# Schematic.net
KiCad netlist of a schematic drawn in EasyEDA
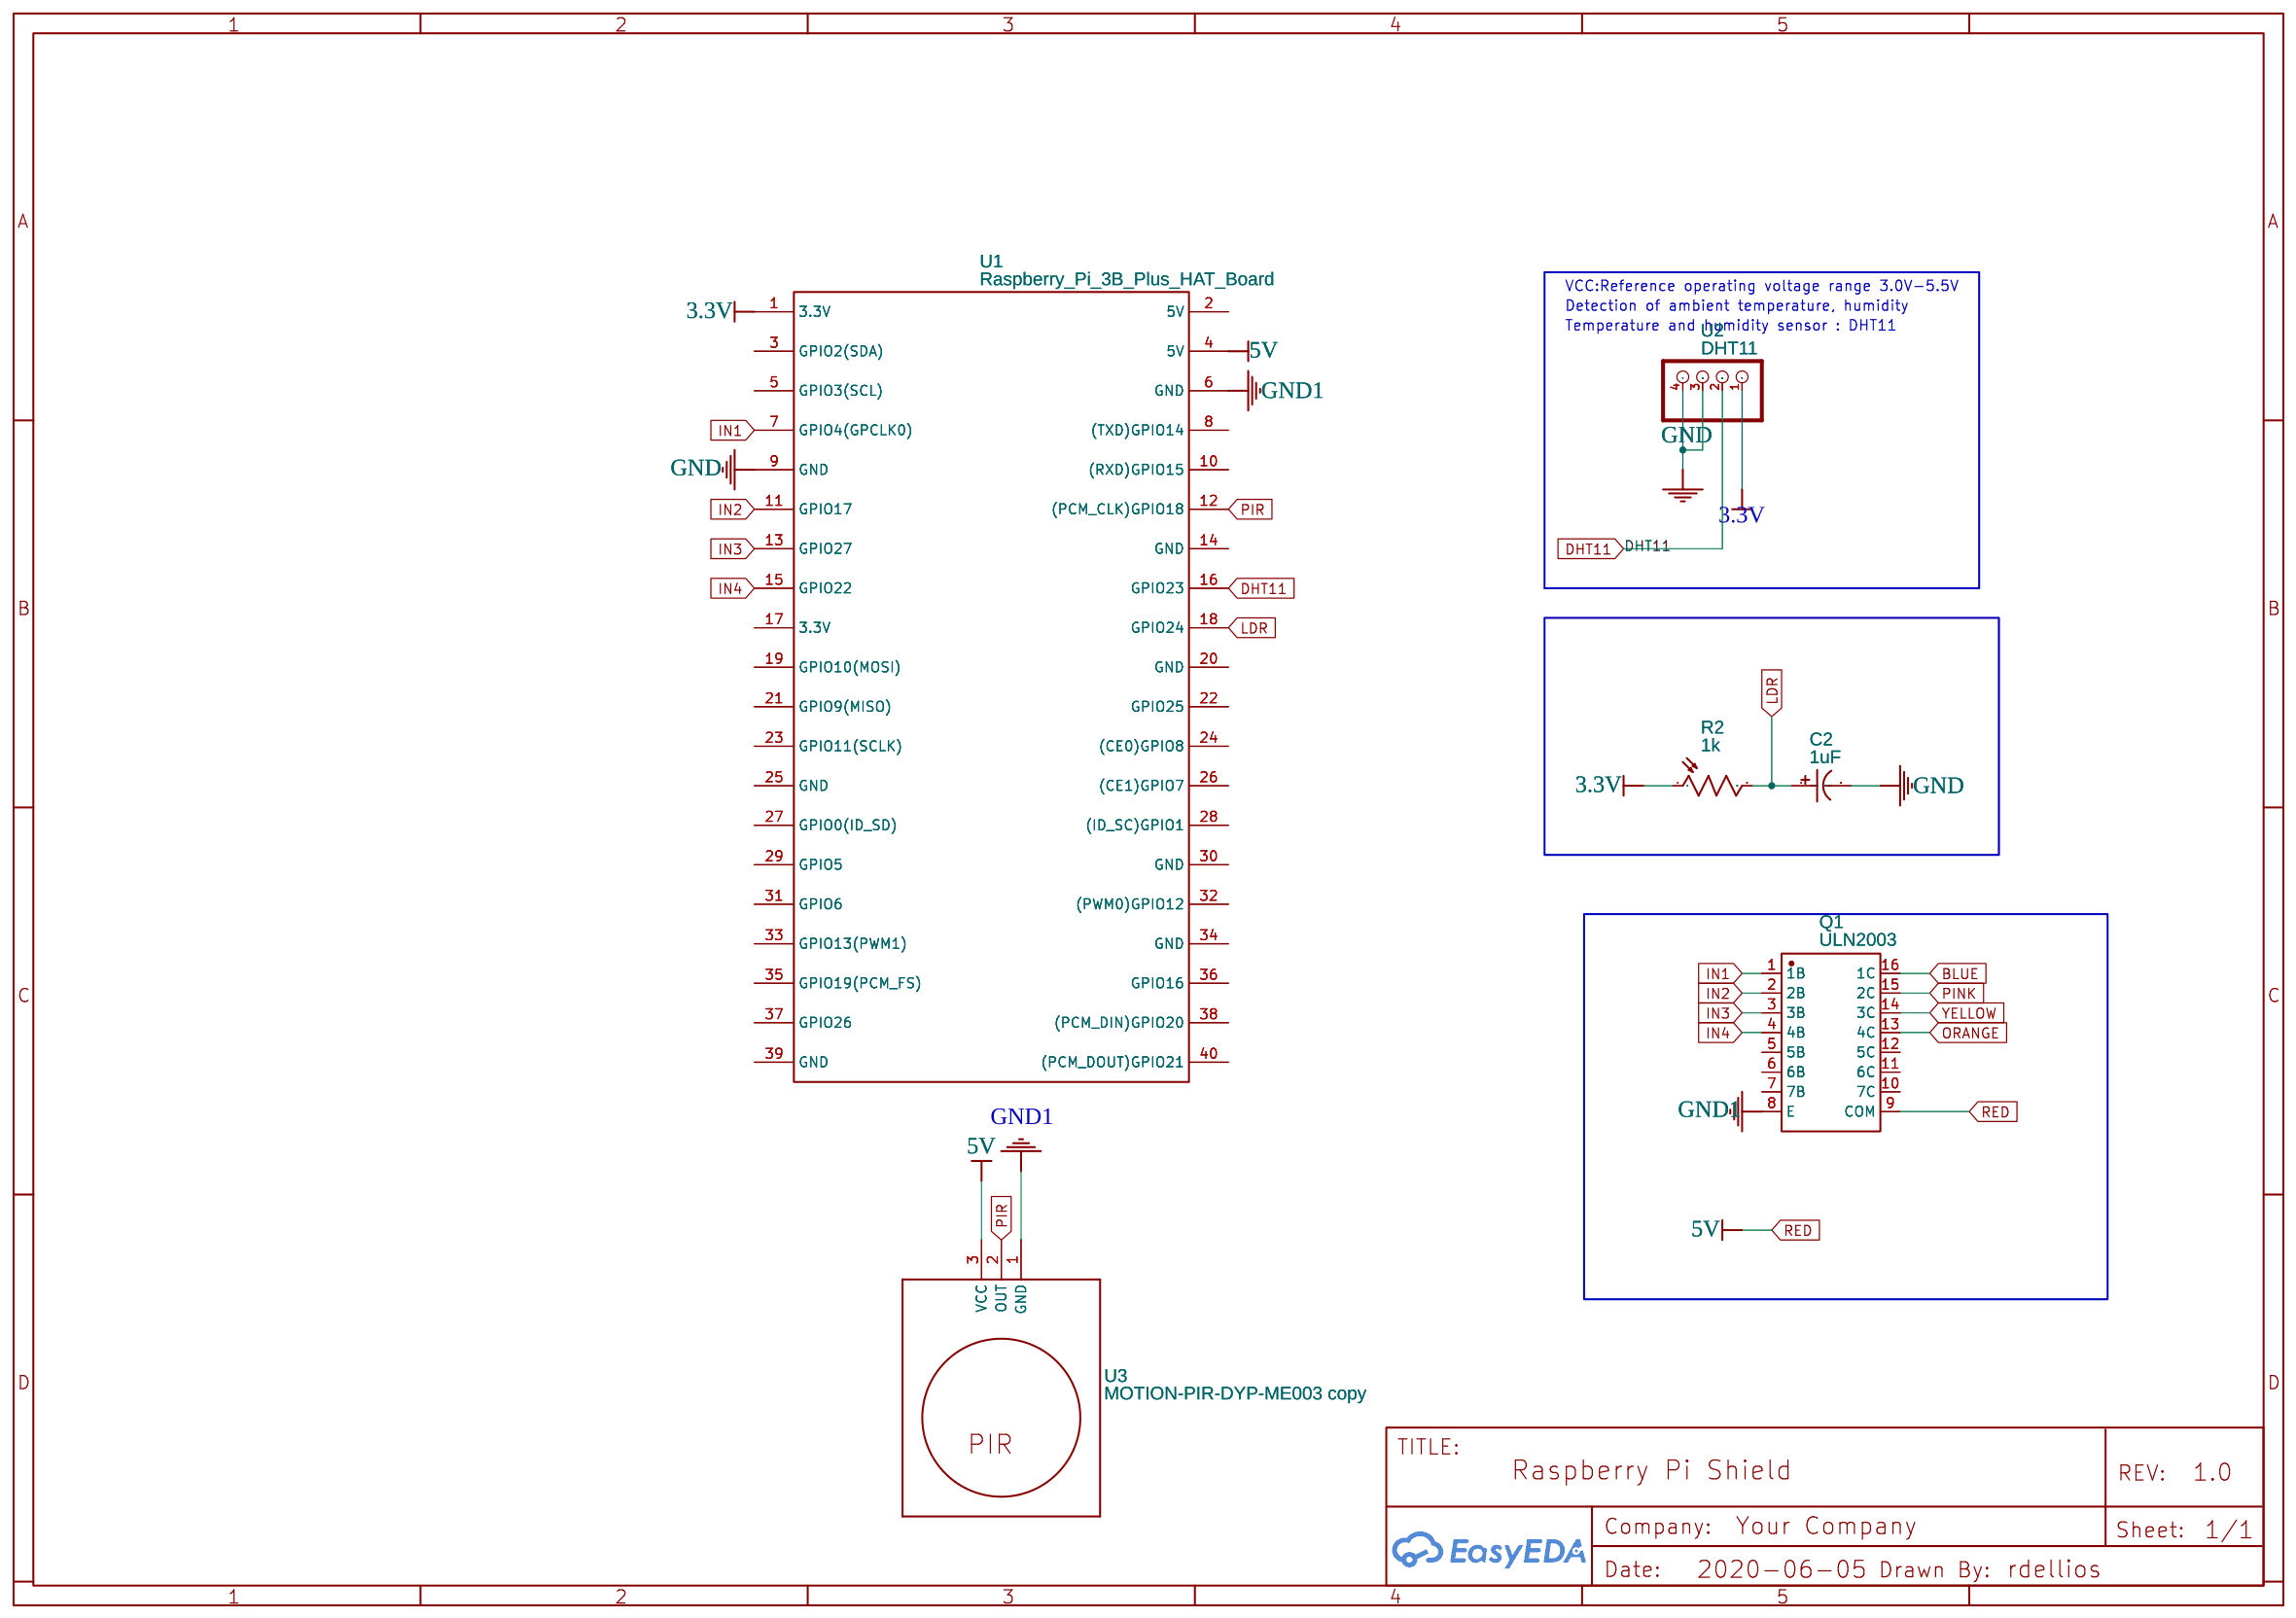
[diagram p0: schematic sheet]

(export (version "E")
  (design (tool "Eeschema 10.0.6"))
  (components
    (comp (ref "C2")
      (value "1uF")
      (fields
        (field (name "BOM_Manufacturer Part") "1uF 50V 4*5")
        (field (name "BOM_Supplier Part") "C47848")
      )
      (libsource (lib "") (part "1uF 50V 4*5"))
    )
    (comp (ref "Q1")
      (value "ULN2003")
      (fields (field (name "BOM_Supplier Part") "C411052"))
      (libsource (lib "") (part "ULN2003"))
    )
    (comp (ref "R2") (value "1k") (libsource (lib "") (part "PhotoResistor")))
    (comp (ref "U1")
      (value "Raspberry_Pi_3B_Plus_HAT_Board")
      (fields (field (name "BOM_Manufacturer Part") "Raspberry-Pi-3B-Plus-HAT-Board"))
      (libsource (lib "") (part "Raspberry_Pi_3B_Plus_HAT_Board"))
    )
    (comp (ref "U2")
      (value "DHT11")
      (fields (field (name "BOM_Manufacturer Part") "?"))
      (libsource (lib "") (part "Unknown_825_-595"))
    )
    (comp (ref "U3")
      (value "MOTION-PIR-DYP-ME003 copy")
      (libsource (lib "") (part "MOTION-PIR-DYP-ME003 copy"))
    )
  )
  (nets
    (net (code "1") (name "3.3V") (class "Default")
      (node (ref "R2") (pin "1") (pinfunction "1_1") (pintype "unspecified"))
      (node (ref "U1") (pin "1") (pinfunction "3.3V_1") (pintype "unspecified"))
      (node (ref "U2") (pin "1") (pinfunction "1_1") (pintype "unspecified"))
    )
    (net (code "2") (name "BLUE") (class "Default")
      (node (ref "Q1") (pin "16") (pinfunction "1C_16") (pintype "unspecified"))
    )
    (net (code "3") (name "DHT11") (class "Default")
      (node (ref "U1") (pin "16") (pinfunction "GPIO23_16") (pintype "unspecified"))
      (node (ref "U2") (pin "2") (pinfunction "2_2") (pintype "unspecified"))
    )
    (net (code "4") (name "GND") (class "Default")
      (node (ref "C2") (pin "2") (pinfunction "2_2") (pintype "input"))
      (node (ref "U1") (pin "9") (pinfunction "GND_9") (pintype "unspecified"))
      (node (ref "U2") (pin "3") (pinfunction "3_3") (pintype "unspecified"))
      (node (ref "U2") (pin "4") (pinfunction "4_4") (pintype "unspecified"))
    )
    (net (code "5") (name "GND1") (class "Default")
      (node (ref "Q1") (pin "8") (pinfunction "E_8") (pintype "unspecified"))
      (node (ref "U1") (pin "6") (pinfunction "GND_6") (pintype "unspecified"))
      (node (ref "U3") (pin "1") (pinfunction "GND_1") (pintype "passive"))
    )
    (net (code "6") (name "IN1") (class "Default")
      (node (ref "Q1") (pin "1") (pinfunction "1B_1") (pintype "unspecified"))
      (node (ref "U1") (pin "7") (pinfunction "GPIO4(GPCLK0)_7") (pintype "unspecified"))
    )
    (net (code "7") (name "IN2") (class "Default")
      (node (ref "Q1") (pin "2") (pinfunction "2B_2") (pintype "unspecified"))
      (node (ref "U1") (pin "11") (pinfunction "GPIO17_11") (pintype "unspecified"))
    )
    (net (code "8") (name "IN3") (class "Default")
      (node (ref "Q1") (pin "3") (pinfunction "3B_3") (pintype "unspecified"))
      (node (ref "U1") (pin "13") (pinfunction "GPIO27_13") (pintype "unspecified"))
    )
    (net (code "9") (name "IN4") (class "Default")
      (node (ref "Q1") (pin "4") (pinfunction "4B_4") (pintype "unspecified"))
      (node (ref "U1") (pin "15") (pinfunction "GPIO22_15") (pintype "unspecified"))
    )
    (net (code "10") (name "LDR") (class "Default")
      (node (ref "C2") (pin "1") (pinfunction "1_1") (pintype "input"))
      (node (ref "R2") (pin "2") (pinfunction "2_2") (pintype "unspecified"))
      (node (ref "U1") (pin "18") (pinfunction "GPIO24_18") (pintype "unspecified"))
    )
    (net (code "11") (name "ORANGE") (class "Default")
      (node (ref "Q1") (pin "13") (pinfunction "4C_13") (pintype "unspecified"))
    )
    (net (code "12") (name "PINK") (class "Default")
      (node (ref "Q1") (pin "15") (pinfunction "2C_15") (pintype "unspecified"))
    )
    (net (code "13") (name "PIR") (class "Default")
      (node (ref "U1") (pin "12") (pinfunction "(PCM_CLK)GPIO18_12") (pintype "unspecified"))
      (node (ref "U3") (pin "2") (pinfunction "OUT_2") (pintype "output"))
    )
    (net (code "14") (name "RED") (class "Default")
      (node (ref "Q1") (pin "9") (pinfunction "COM_9") (pintype "unspecified"))
      (node (ref "U1") (pin "4") (pinfunction "5V_4") (pintype "unspecified"))
      (node (ref "U3") (pin "3") (pinfunction "VCC_3") (pintype "passive"))
    )
    (net (code "15") (name "YELLOW") (class "Default")
      (node (ref "Q1") (pin "14") (pinfunction "3C_14") (pintype "unspecified"))
    )
    (net (code "16") (name "unconnected-(Q1-5B-Pad5)") (class "Default")
      (node (ref "Q1") (pin "5") (pinfunction "5B_5") (pintype "unspecified"))
    )
    (net (code "17") (name "unconnected-(Q1-5C-Pad12)") (class "Default")
      (node (ref "Q1") (pin "12") (pinfunction "5C_12") (pintype "unspecified"))
    )
    (net (code "18") (name "unconnected-(Q1-6B-Pad6)") (class "Default")
      (node (ref "Q1") (pin "6") (pinfunction "6B_6") (pintype "unspecified"))
    )
    (net (code "19") (name "unconnected-(Q1-6C-Pad11)") (class "Default")
      (node (ref "Q1") (pin "11") (pinfunction "6C_11") (pintype "unspecified"))
    )
    (net (code "20") (name "unconnected-(Q1-7B-Pad7)") (class "Default")
      (node (ref "Q1") (pin "7") (pinfunction "7B_7") (pintype "unspecified"))
    )
    (net (code "21") (name "unconnected-(Q1-7C-Pad10)") (class "Default")
      (node (ref "Q1") (pin "10") (pinfunction "7C_10") (pintype "unspecified"))
    )
    (net (code "22") (name "unconnected-(U1-(CE0)GPIO8-Pad24)") (class "Default")
      (node (ref "U1") (pin "24") (pinfunction "(CE0)GPIO8_24") (pintype "unspecified"))
    )
    (net (code "23") (name "unconnected-(U1-(CE1)GPIO7-Pad26)") (class "Default")
      (node (ref "U1") (pin "26") (pinfunction "(CE1)GPIO7_26") (pintype "unspecified"))
    )
    (net (code "24") (name "unconnected-(U1-(ID_SC)GPIO1-Pad28)") (class "Default")
      (node (ref "U1") (pin "28") (pinfunction "(ID_SC)GPIO1_28") (pintype "unspecified"))
    )
    (net (code "25") (name "unconnected-(U1-(PCM_DIN)GPIO20-Pad38)") (class "Default")
      (node (ref "U1") (pin "38") (pinfunction "(PCM_DIN)GPIO20_38") (pintype "unspecified"))
    )
    (net (code "26") (name "unconnected-(U1-(PCM_DOUT)GPIO21-Pad40)") (class "Default")
      (node (ref "U1") (pin "40") (pinfunction "(PCM_DOUT)GPIO21_40") (pintype "unspecified"))
    )
    (net (code "27") (name "unconnected-(U1-(PWM0)GPIO12-Pad32)") (class "Default")
      (node (ref "U1") (pin "32") (pinfunction "(PWM0)GPIO12_32") (pintype "unspecified"))
    )
    (net (code "28") (name "unconnected-(U1-(RXD)GPIO15-Pad10)") (class "Default")
      (node (ref "U1") (pin "10") (pinfunction "(RXD)GPIO15_10") (pintype "unspecified"))
    )
    (net (code "29") (name "unconnected-(U1-(TXD)GPIO14-Pad8)") (class "Default")
      (node (ref "U1") (pin "8") (pinfunction "(TXD)GPIO14_8") (pintype "unspecified"))
    )
    (net (code "30") (name "unconnected-(U1-3.3V-Pad17)") (class "Default")
      (node (ref "U1") (pin "17") (pinfunction "3.3V_17") (pintype "unspecified"))
    )
    (net (code "31") (name "unconnected-(U1-5V-Pad2)") (class "Default")
      (node (ref "U1") (pin "2") (pinfunction "5V_2") (pintype "unspecified"))
    )
    (net (code "32") (name "unconnected-(U1-GND-Pad14)") (class "Default")
      (node (ref "U1") (pin "14") (pinfunction "GND_14") (pintype "unspecified"))
    )
    (net (code "33") (name "unconnected-(U1-GND-Pad20)") (class "Default")
      (node (ref "U1") (pin "20") (pinfunction "GND_20") (pintype "unspecified"))
    )
    (net (code "34") (name "unconnected-(U1-GND-Pad25)") (class "Default")
      (node (ref "U1") (pin "25") (pinfunction "GND_25") (pintype "unspecified"))
    )
    (net (code "35") (name "unconnected-(U1-GND-Pad30)") (class "Default")
      (node (ref "U1") (pin "30") (pinfunction "GND_30") (pintype "unspecified"))
    )
    (net (code "36") (name "unconnected-(U1-GND-Pad34)") (class "Default")
      (node (ref "U1") (pin "34") (pinfunction "GND_34") (pintype "unspecified"))
    )
    (net (code "37") (name "unconnected-(U1-GND-Pad39)") (class "Default")
      (node (ref "U1") (pin "39") (pinfunction "GND_39") (pintype "unspecified"))
    )
    (net (code "38") (name "unconnected-(U1-GPIO0(ID_SD)-Pad27)") (class "Default")
      (node (ref "U1") (pin "27") (pinfunction "GPIO0(ID_SD)_27") (pintype "unspecified"))
    )
    (net (code "39") (name "unconnected-(U1-GPIO2(SDA)-Pad3)") (class "Default")
      (node (ref "U1") (pin "3") (pinfunction "GPIO2(SDA)_3") (pintype "unspecified"))
    )
    (net (code "40") (name "unconnected-(U1-GPIO3(SCL)-Pad5)") (class "Default")
      (node (ref "U1") (pin "5") (pinfunction "GPIO3(SCL)_5") (pintype "unspecified"))
    )
    (net (code "41") (name "unconnected-(U1-GPIO5-Pad29)") (class "Default")
      (node (ref "U1") (pin "29") (pinfunction "GPIO5_29") (pintype "unspecified"))
    )
    (net (code "42") (name "unconnected-(U1-GPIO6-Pad31)") (class "Default")
      (node (ref "U1") (pin "31") (pinfunction "GPIO6_31") (pintype "unspecified"))
    )
    (net (code "43") (name "unconnected-(U1-GPIO9(MISO)-Pad21)") (class "Default")
      (node (ref "U1") (pin "21") (pinfunction "GPIO9(MISO)_21") (pintype "unspecified"))
    )
    (net (code "44") (name "unconnected-(U1-GPIO10(MOSI)-Pad19)") (class "Default")
      (node (ref "U1") (pin "19") (pinfunction "GPIO10(MOSI)_19") (pintype "unspecified"))
    )
    (net (code "45") (name "unconnected-(U1-GPIO11(SCLK)-Pad23)") (class "Default")
      (node (ref "U1") (pin "23") (pinfunction "GPIO11(SCLK)_23") (pintype "unspecified"))
    )
    (net (code "46") (name "unconnected-(U1-GPIO13(PWM1)-Pad33)") (class "Default")
      (node (ref "U1") (pin "33") (pinfunction "GPIO13(PWM1)_33") (pintype "unspecified"))
    )
    (net (code "47") (name "unconnected-(U1-GPIO16-Pad36)") (class "Default")
      (node (ref "U1") (pin "36") (pinfunction "GPIO16_36") (pintype "unspecified"))
    )
    (net (code "48") (name "unconnected-(U1-GPIO19(PCM_FS)-Pad35)") (class "Default")
      (node (ref "U1") (pin "35") (pinfunction "GPIO19(PCM_FS)_35") (pintype "unspecified"))
    )
    (net (code "49") (name "unconnected-(U1-GPIO25-Pad22)") (class "Default")
      (node (ref "U1") (pin "22") (pinfunction "GPIO25_22") (pintype "unspecified"))
    )
    (net (code "50") (name "unconnected-(U1-GPIO26-Pad37)") (class "Default")
      (node (ref "U1") (pin "37") (pinfunction "GPIO26_37") (pintype "unspecified"))
    )
  )
)
